# ControlBoard_mk2.net
KiCad netlist of a schematic drawn in Altium Designer
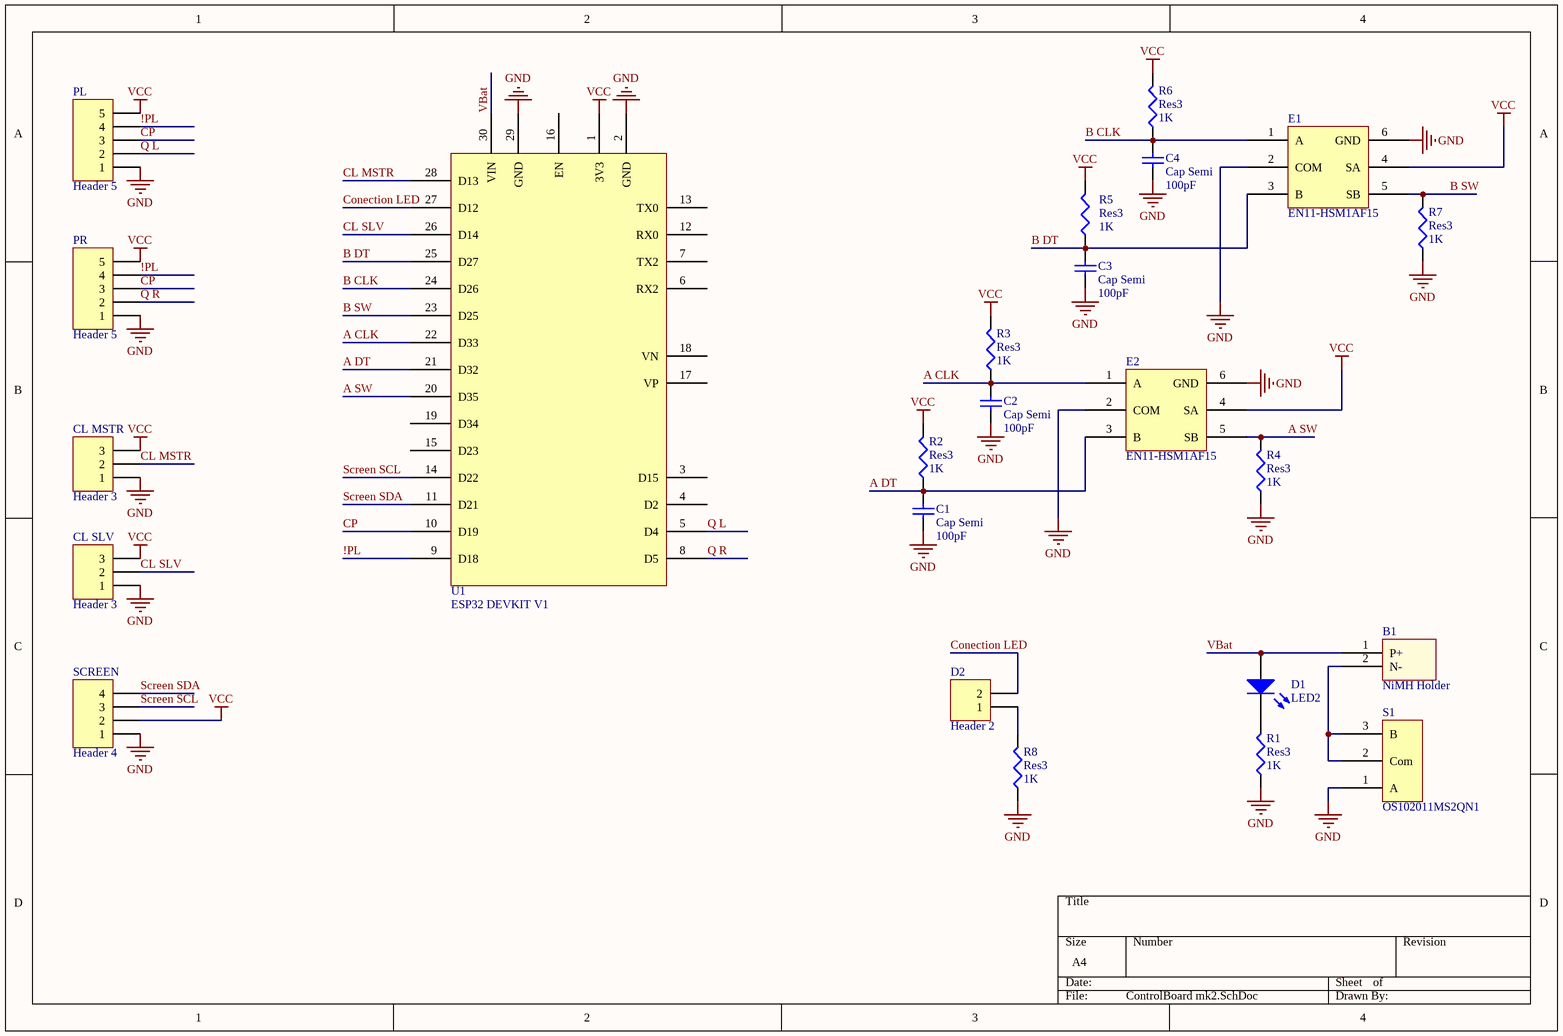
[diagram p0: ControlBoard mk2.SchDoc]

(export (version "E")
  (design (tool "Eeschema 10.0.6"))
  (components
    (comp (ref "B1")
      (value "NiMH Holder")
      (footprint "NiMH Holder")
      (libsource (lib "WheelLib") (part "NiMH Holder"))
    )
    (comp (ref "C1")
      (value "Cap Semi")
      (footprint "WheelLibrary:0603 Cap Long Boi")
      (description "Capacitor (Semiconductor SIM Model)")
      (fields (field (name "ALTIUM_VALUE") "100pF") (field (name "PUBLISHER") "Altium Limited"))
      (libsource (lib "Miscellaneous Devices") (part "Cap Semi"))
    )
    (comp (ref "C2")
      (value "Cap Semi")
      (footprint "WheelLibrary:0603 Cap Long Boi")
      (description "Capacitor (Semiconductor SIM Model)")
      (fields (field (name "ALTIUM_VALUE") "100pF") (field (name "PUBLISHER") "Altium Limited"))
      (libsource (lib "Miscellaneous Devices") (part "Cap Semi"))
    )
    (comp (ref "C3")
      (value "Cap Semi")
      (footprint "WheelLibrary:0603 Cap Long Boi")
      (description "Capacitor (Semiconductor SIM Model)")
      (fields (field (name "ALTIUM_VALUE") "100pF") (field (name "PUBLISHER") "Altium Limited"))
      (libsource (lib "Miscellaneous Devices") (part "Cap Semi"))
    )
    (comp (ref "C4")
      (value "Cap Semi")
      (footprint "WheelLibrary:0603 Cap Long Boi")
      (description "Capacitor (Semiconductor SIM Model)")
      (fields (field (name "ALTIUM_VALUE") "100pF") (field (name "PUBLISHER") "Altium Limited"))
      (libsource (lib "Miscellaneous Devices") (part "Cap Semi"))
    )
    (comp (ref "CL MSTR")
      (value "Header 3")
      (footprint "WheelLibrary:3 Pin Side Mount")
      (description "Header, 3-Pin")
      (fields (field (name "PUBLISHER") "Altium Limited"))
      (libsource (lib "Miscellaneous Connectors") (part "Header 3"))
    )
    (comp (ref "CL SLV")
      (value "Header 3")
      (footprint "WheelLibrary:3 Pin Side Mount")
      (description "Header, 3-Pin")
      (fields (field (name "PUBLISHER") "Altium Limited"))
      (libsource (lib "Miscellaneous Connectors") (part "Header 3"))
    )
    (comp (ref "D1")
      (value "LED2")
      (footprint "LTST-C171TBKT")
      (description "Typical RED, GREEN, YELLOW, AMBER GaAs LED")
      (fields (field (name "PUBLISHER") "Altium Limited"))
      (libsource (lib "Miscellaneous Devices") (part "LED2"))
    )
    (comp (ref "D2")
      (value "Header 2")
      (footprint "HDR1X2")
      (description "Header, 2-Pin")
      (fields (field (name "PUBLISHER") "Altium Limited"))
      (libsource (lib "Miscellaneous Connectors") (part "Header 2"))
    )
    (comp (ref "E1")
      (value "EN11-HSM1AF15")
      (footprint "EN11-HSM1AF15")
      (libsource (lib "WheelLib") (part "EN11-HSM1AF15"))
    )
    (comp (ref "E2")
      (value "EN11-HSM1AF15")
      (footprint "EN11-HSM1AF15")
      (libsource (lib "WheelLib") (part "EN11-HSM1AF15"))
    )
    (comp (ref "PL")
      (value "Header 5")
      (footprint "WheelLibrary:5 Pin Side Mount")
      (description "Header, 5-Pin")
      (fields (field (name "PUBLISHER") "Altium Limited"))
      (libsource (lib "Miscellaneous Connectors") (part "Header 5"))
    )
    (comp (ref "PR")
      (value "Header 5")
      (footprint "HDR1X5")
      (description "Header, 5-Pin")
      (fields (field (name "PUBLISHER") "Altium Limited"))
      (libsource (lib "Miscellaneous Connectors") (part "Header 5"))
    )
    (comp (ref "R1")
      (value "Res3")
      (footprint "WheelLibrary:0603 Res Long Boi - duplicate")
      (description "Resistor")
      (fields (field (name "ALTIUM_VALUE") "1K") (field (name "PUBLISHER") "Altium Limited"))
      (libsource (lib "Miscellaneous Devices") (part "Res3"))
    )
    (comp (ref "R2")
      (value "Res3")
      (footprint "WheelLibrary:0603 Res Long Boi - duplicate")
      (description "Resistor")
      (fields (field (name "ALTIUM_VALUE") "1K") (field (name "PUBLISHER") "Altium Limited"))
      (libsource (lib "Miscellaneous Devices") (part "Res3"))
    )
    (comp (ref "R3")
      (value "Res3")
      (footprint "WheelLibrary:0603 Res Long Boi - duplicate")
      (description "Resistor")
      (fields (field (name "ALTIUM_VALUE") "1K") (field (name "PUBLISHER") "Altium Limited"))
      (libsource (lib "Miscellaneous Devices") (part "Res3"))
    )
    (comp (ref "R4")
      (value "Res3")
      (footprint "WheelLibrary:0603 Res Long Boi - duplicate")
      (description "Resistor")
      (fields (field (name "ALTIUM_VALUE") "1K") (field (name "PUBLISHER") "Altium Limited"))
      (libsource (lib "Miscellaneous Devices") (part "Res3"))
    )
    (comp (ref "R5")
      (value "Res3")
      (footprint "WheelLibrary:0603 Res Long Boi - duplicate")
      (description "Resistor")
      (fields (field (name "ALTIUM_VALUE") "1K") (field (name "PUBLISHER") "Altium Limited"))
      (libsource (lib "Miscellaneous Devices") (part "Res3"))
    )
    (comp (ref "R6")
      (value "Res3")
      (footprint "WheelLibrary:0603 Res Long Boi - duplicate")
      (description "Resistor")
      (fields (field (name "ALTIUM_VALUE") "1K") (field (name "PUBLISHER") "Altium Limited"))
      (libsource (lib "Miscellaneous Devices") (part "Res3"))
    )
    (comp (ref "R7")
      (value "Res3")
      (footprint "WheelLibrary:0603 Res Long Boi - duplicate")
      (description "Resistor")
      (fields (field (name "ALTIUM_VALUE") "1K") (field (name "PUBLISHER") "Altium Limited"))
      (libsource (lib "Miscellaneous Devices") (part "Res3"))
    )
    (comp (ref "R8")
      (value "Res3")
      (footprint "WheelLibrary:0603 Res Long Boi - duplicate")
      (description "Resistor")
      (fields (field (name "ALTIUM_VALUE") "1K") (field (name "PUBLISHER") "Altium Limited"))
      (libsource (lib "Miscellaneous Devices") (part "Res3"))
    )
    (comp (ref "S1")
      (value "OS102011MS2QN1")
      (footprint "OS102011MS2QN1")
      (libsource (lib "WheelLib") (part "OS102011MS2QN1"))
    )
    (comp (ref "SCREEN")
      (value "Header 4")
      (footprint "WheelLibrary:4 Pin Side Mount")
      (description "Header, 4-Pin")
      (fields (field (name "PUBLISHER") "Altium Limited"))
      (libsource (lib "Miscellaneous Connectors") (part "Header 4"))
    )
    (comp (ref "U1")
      (value "ESP32 DEVKIT V1")
      (footprint "ESP32 DEVKIT V1")
      (libsource (lib "WheelLib") (part "ESP32 DEVKIT V1"))
    )
  )
  (nets
    (net (code "1") (name "/!PL") (class "Default")
      (node (ref "PL") (pin "4") (pinfunction "4_4") (pintype "passive"))
      (node (ref "PR") (pin "4") (pinfunction "4_4") (pintype "passive"))
      (node (ref "U1") (pin "9") (pinfunction "D18_9") (pintype "passive"))
    )
    (net (code "2") (name "/A CLK") (class "Default")
      (node (ref "C2") (pin "2") (pinfunction "2_2") (pintype "passive"))
      (node (ref "E2") (pin "1") (pinfunction "A_1") (pintype "passive"))
      (node (ref "R3") (pin "1") (pinfunction "1_1") (pintype "passive"))
      (node (ref "U1") (pin "22") (pinfunction "D33_22") (pintype "passive"))
    )
    (net (code "3") (name "/A DT") (class "Default")
      (node (ref "C1") (pin "1") (pinfunction "1_1") (pintype "passive"))
      (node (ref "E2") (pin "3") (pinfunction "B_3") (pintype "passive"))
      (node (ref "R2") (pin "1") (pinfunction "1_1") (pintype "passive"))
      (node (ref "U1") (pin "21") (pinfunction "D32_21") (pintype "passive"))
    )
    (net (code "4") (name "/A SW") (class "Default")
      (node (ref "E2") (pin "5") (pinfunction "SB_5") (pintype "passive"))
      (node (ref "R4") (pin "2") (pinfunction "2_2") (pintype "passive"))
      (node (ref "U1") (pin "20") (pinfunction "D35_20") (pintype "passive"))
    )
    (net (code "5") (name "/B CLK") (class "Default")
      (node (ref "C4") (pin "2") (pinfunction "2_2") (pintype "passive"))
      (node (ref "E1") (pin "1") (pinfunction "A_1") (pintype "passive"))
      (node (ref "R6") (pin "1") (pinfunction "1_1") (pintype "passive"))
      (node (ref "U1") (pin "24") (pinfunction "D26_24") (pintype "passive"))
    )
    (net (code "6") (name "/B DT") (class "Default")
      (node (ref "C3") (pin "1") (pinfunction "1_1") (pintype "passive"))
      (node (ref "E1") (pin "3") (pinfunction "B_3") (pintype "passive"))
      (node (ref "R5") (pin "1") (pinfunction "1_1") (pintype "passive"))
      (node (ref "U1") (pin "25") (pinfunction "D27_25") (pintype "passive"))
    )
    (net (code "7") (name "/B SW") (class "Default")
      (node (ref "E1") (pin "5") (pinfunction "SB_5") (pintype "passive"))
      (node (ref "R7") (pin "2") (pinfunction "2_2") (pintype "passive"))
      (node (ref "U1") (pin "23") (pinfunction "D25_23") (pintype "passive"))
    )
    (net (code "8") (name "/CL MSTR") (class "Default")
      (node (ref "CL MSTR") (pin "2") (pinfunction "2_2") (pintype "passive"))
      (node (ref "U1") (pin "28") (pinfunction "D13_28") (pintype "passive"))
    )
    (net (code "9") (name "/CL SLV") (class "Default")
      (node (ref "CL SLV") (pin "2") (pinfunction "2_2") (pintype "passive"))
      (node (ref "U1") (pin "26") (pinfunction "D14_26") (pintype "passive"))
    )
    (net (code "10") (name "/CP") (class "Default")
      (node (ref "PL") (pin "3") (pinfunction "3_3") (pintype "passive"))
      (node (ref "PR") (pin "3") (pinfunction "3_3") (pintype "passive"))
      (node (ref "U1") (pin "10") (pinfunction "D19_10") (pintype "passive"))
    )
    (net (code "11") (name "/Conection LED") (class "Default")
      (node (ref "D2") (pin "2") (pinfunction "2_2") (pintype "passive"))
      (node (ref "U1") (pin "27") (pinfunction "D12_27") (pintype "passive"))
    )
    (net (code "12") (name "/Q L") (class "Default")
      (node (ref "PL") (pin "2") (pinfunction "2_2") (pintype "passive"))
      (node (ref "U1") (pin "5") (pinfunction "D4_5") (pintype "passive"))
    )
    (net (code "13") (name "/Q R") (class "Default")
      (node (ref "PR") (pin "2") (pinfunction "2_2") (pintype "passive"))
      (node (ref "U1") (pin "8") (pinfunction "D5_8") (pintype "passive"))
    )
    (net (code "14") (name "/Screen SCL") (class "Default")
      (node (ref "SCREEN") (pin "3") (pinfunction "3_3") (pintype "passive"))
      (node (ref "U1") (pin "14") (pinfunction "D22_14") (pintype "passive"))
    )
    (net (code "15") (name "/Screen SDA") (class "Default")
      (node (ref "SCREEN") (pin "4") (pinfunction "4_4") (pintype "passive"))
      (node (ref "U1") (pin "11") (pinfunction "D21_11") (pintype "passive"))
    )
    (net (code "16") (name "/VBat") (class "Default")
      (node (ref "B1") (pin "1") (pinfunction "P+_1") (pintype "power_in"))
      (node (ref "D1") (pin "1") (pinfunction "A_1") (pintype "passive"))
      (node (ref "U1") (pin "30") (pinfunction "VIN_30") (pintype "passive"))
    )
    (net (code "17") (name "GND") (class "Default")
      (node (ref "C1") (pin "2") (pinfunction "2_2") (pintype "passive"))
      (node (ref "C2") (pin "1") (pinfunction "1_1") (pintype "passive"))
      (node (ref "C3") (pin "2") (pinfunction "2_2") (pintype "passive"))
      (node (ref "C4") (pin "1") (pinfunction "1_1") (pintype "passive"))
      (node (ref "CL MSTR") (pin "1") (pinfunction "1_1") (pintype "passive"))
      (node (ref "CL SLV") (pin "1") (pinfunction "1_1") (pintype "passive"))
      (node (ref "E1") (pin "2") (pinfunction "COM_2") (pintype "passive"))
      (node (ref "E1") (pin "6") (pinfunction "GND_6") (pintype "passive"))
      (node (ref "E2") (pin "2") (pinfunction "COM_2") (pintype "passive"))
      (node (ref "E2") (pin "6") (pinfunction "GND_6") (pintype "passive"))
      (node (ref "PL") (pin "1") (pinfunction "1_1") (pintype "passive"))
      (node (ref "PR") (pin "1") (pinfunction "1_1") (pintype "passive"))
      (node (ref "R1") (pin "1") (pinfunction "1_1") (pintype "passive"))
      (node (ref "R4") (pin "1") (pinfunction "1_1") (pintype "passive"))
      (node (ref "R7") (pin "1") (pinfunction "1_1") (pintype "passive"))
      (node (ref "R8") (pin "1") (pinfunction "1_1") (pintype "passive"))
      (node (ref "S1") (pin "1") (pinfunction "A_1") (pintype "passive"))
      (node (ref "SCREEN") (pin "1") (pinfunction "1_1") (pintype "passive"))
      (node (ref "U1") (pin "2") (pinfunction "GND_2") (pintype "passive"))
      (node (ref "U1") (pin "29") (pinfunction "GND_29") (pintype "passive"))
    )
    (net (code "18") (name "Net-(B1-N-)") (class "Default")
      (node (ref "B1") (pin "2") (pinfunction "N-_2") (pintype "power_in"))
      (node (ref "S1") (pin "2") (pinfunction "Com_2") (pintype "passive"))
      (node (ref "S1") (pin "3") (pinfunction "B_3") (pintype "passive"))
    )
    (net (code "19") (name "Net-(D1-K)") (class "Default")
      (node (ref "D1") (pin "2") (pinfunction "K_2") (pintype "passive"))
      (node (ref "R1") (pin "2") (pinfunction "2_2") (pintype "passive"))
    )
    (net (code "20") (name "Net-(D2-Pad1)") (class "Default")
      (node (ref "D2") (pin "1") (pinfunction "1_1") (pintype "passive"))
      (node (ref "R8") (pin "2") (pinfunction "2_2") (pintype "passive"))
    )
    (net (code "21") (name "VCC") (class "Default")
      (node (ref "CL MSTR") (pin "3") (pinfunction "3_3") (pintype "passive"))
      (node (ref "CL SLV") (pin "3") (pinfunction "3_3") (pintype "passive"))
      (node (ref "E1") (pin "4") (pinfunction "SA_4") (pintype "passive"))
      (node (ref "E2") (pin "4") (pinfunction "SA_4") (pintype "passive"))
      (node (ref "PL") (pin "5") (pinfunction "5_5") (pintype "passive"))
      (node (ref "PR") (pin "5") (pinfunction "5_5") (pintype "passive"))
      (node (ref "R2") (pin "2") (pinfunction "2_2") (pintype "passive"))
      (node (ref "R3") (pin "2") (pinfunction "2_2") (pintype "passive"))
      (node (ref "R5") (pin "2") (pinfunction "2_2") (pintype "passive"))
      (node (ref "R6") (pin "2") (pinfunction "2_2") (pintype "passive"))
      (node (ref "SCREEN") (pin "2") (pinfunction "2_2") (pintype "passive"))
      (node (ref "U1") (pin "1") (pinfunction "3V3_1") (pintype "passive"))
    )
    (net (code "22") (name "unconnected-(U1-D2-Pad4)") (class "Default")
      (node (ref "U1") (pin "4") (pinfunction "D2_4") (pintype "passive"))
    )
    (net (code "23") (name "unconnected-(U1-D15-Pad3)") (class "Default")
      (node (ref "U1") (pin "3") (pinfunction "D15_3") (pintype "passive"))
    )
    (net (code "24") (name "unconnected-(U1-D23-Pad15)") (class "Default")
      (node (ref "U1") (pin "15") (pinfunction "D23_15") (pintype "passive"))
    )
    (net (code "25") (name "unconnected-(U1-D34-Pad19)") (class "Default")
      (node (ref "U1") (pin "19") (pinfunction "D34_19") (pintype "passive"))
    )
    (net (code "26") (name "unconnected-(U1-EN-Pad16)") (class "Default")
      (node (ref "U1") (pin "16") (pinfunction "EN_16") (pintype "passive"))
    )
    (net (code "27") (name "unconnected-(U1-RX0-Pad12)") (class "Default")
      (node (ref "U1") (pin "12") (pinfunction "RX0_12") (pintype "passive"))
    )
    (net (code "28") (name "unconnected-(U1-RX2-Pad6)") (class "Default")
      (node (ref "U1") (pin "6") (pinfunction "RX2_6") (pintype "passive"))
    )
    (net (code "29") (name "unconnected-(U1-TX0-Pad13)") (class "Default")
      (node (ref "U1") (pin "13") (pinfunction "TX0_13") (pintype "passive"))
    )
    (net (code "30") (name "unconnected-(U1-TX2-Pad7)") (class "Default")
      (node (ref "U1") (pin "7") (pinfunction "TX2_7") (pintype "passive"))
    )
    (net (code "31") (name "unconnected-(U1-VN-Pad18)") (class "Default")
      (node (ref "U1") (pin "18") (pinfunction "VN_18") (pintype "passive"))
    )
    (net (code "32") (name "unconnected-(U1-VP-Pad17)") (class "Default")
      (node (ref "U1") (pin "17") (pinfunction "VP_17") (pintype "passive"))
    )
  )
)
